# RC_Inverter.net
KiCad netlist of a schematic drawn in Altium Designer
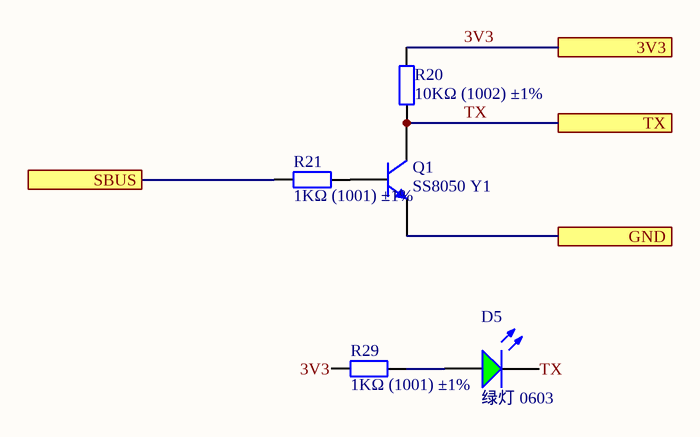
[diagram p0: RC_Inverter.SchDoc]

(export (version "E")
  (design (tool "Eeschema 10.0.6"))
  (components
    (comp (ref "D5")
      (value "绿灯 0603")
      (footprint "0603_LED_S1")
      (description "发光二极管")
      (libsource (lib "Miscellaneous Devices LC") (part "0603 绿灯"))
    )
    (comp (ref "Q1")
      (value "SS8050 Y1")
      (footprint "SOT-23(SOT-23-3)")
      (description "三极管")
      (libsource (lib "Miscellaneous Devices LC") (part "SOT-23 SS8050 Y1"))
    )
    (comp (ref "R20")
      (value "10KΩ (1002) ±1%")
      (footprint "0402_R")
      (description "贴片电阻")
      (libsource (lib "Miscellaneous Devices LC") (part "0402 10KΩ (1002) 1%"))
    )
    (comp (ref "R21")
      (value "1KΩ (1001) ±1%")
      (footprint "0402_R")
      (description "贴片电阻")
      (libsource (lib "Miscellaneous Devices LC") (part "0402 1KΩ (1001) 1%"))
    )
    (comp (ref "R29")
      (value "1KΩ (1001) ±1%")
      (footprint "0402_R")
      (description "贴片电阻")
      (libsource (lib "Miscellaneous Devices LC") (part "0402 1KΩ (1001) 1%"))
    )
  )
  (nets
    (net (code "1") (name "/3V3") (class "Default")
      (node (ref "R20") (pin "2") (pinfunction "2_2") (pintype "passive"))
      (node (ref "R29") (pin "1") (pinfunction "1_1") (pintype "passive"))
    )
    (net (code "2") (name "/GND") (class "Default")
      (node (ref "Q1") (pin "2") (pinfunction "E_2") (pintype "passive"))
    )
    (net (code "3") (name "/SBUS") (class "Default")
      (node (ref "R21") (pin "1") (pinfunction "1_1") (pintype "passive"))
    )
    (net (code "4") (name "/TX") (class "Default")
      (node (ref "D5") (pin "K") (pinfunction "K_K") (pintype "passive"))
      (node (ref "Q1") (pin "3") (pinfunction "C_3") (pintype "passive"))
      (node (ref "R20") (pin "1") (pinfunction "1_1") (pintype "passive"))
    )
    (net (code "5") (name "Net-(D5-PadA)") (class "Default")
      (node (ref "D5") (pin "A") (pinfunction "A_A") (pintype "passive"))
      (node (ref "R29") (pin "2") (pinfunction "2_2") (pintype "passive"))
    )
    (net (code "6") (name "Net-(Q1-B)") (class "Default")
      (node (ref "Q1") (pin "1") (pinfunction "B_1") (pintype "passive"))
      (node (ref "R21") (pin "2") (pinfunction "2_2") (pintype "passive"))
    )
  )
)
